# Grove_Base_Shield_for_NodeMCU_v1_0.net
KiCad netlist of a schematic drawn in EAGLE
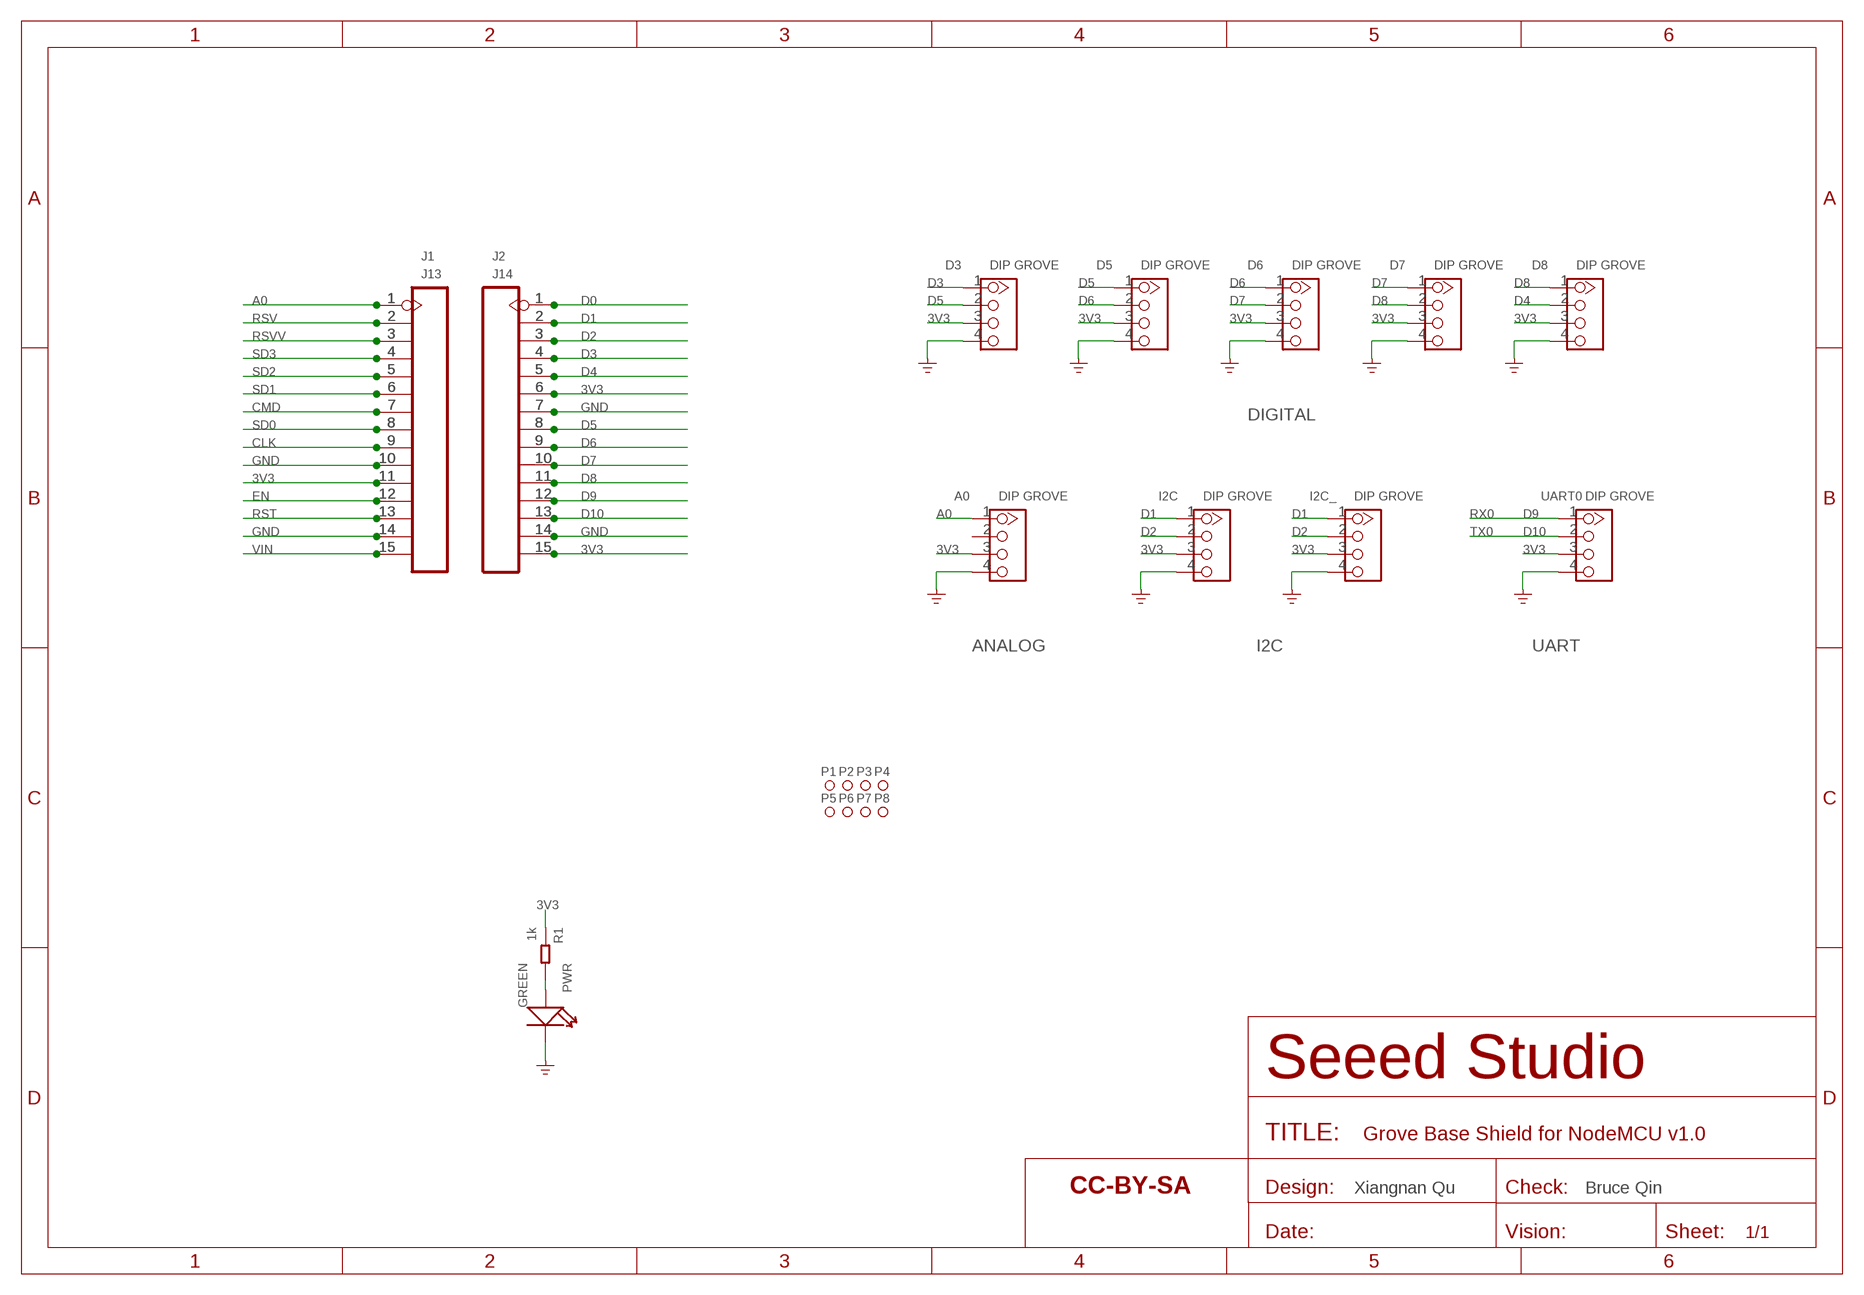
[diagram p0: schematic, sheet 1]

(export (version "E")
  (design (tool "Eeschema 10.0.6"))
  (components
    (comp (ref "A0")
      (value "DIP GROVE")
      (footprint "eagle-import:HW4-2.0")
      (libsource (lib "eagle-import") (part "GROVE-CONNECTOR-DIP-2.0"))
    )
    (comp (ref "D3")
      (value "DIP GROVE")
      (footprint "eagle-import:HW4-2.0")
      (libsource (lib "eagle-import") (part "GROVE-CONNECTOR-DIP-2.0"))
    )
    (comp (ref "D5")
      (value "DIP GROVE")
      (footprint "eagle-import:HW4-2.0")
      (libsource (lib "eagle-import") (part "GROVE-CONNECTOR-DIP-2.0"))
    )
    (comp (ref "D6")
      (value "DIP GROVE")
      (footprint "eagle-import:HW4-2.0")
      (libsource (lib "eagle-import") (part "GROVE-CONNECTOR-DIP-2.0"))
    )
    (comp (ref "D7")
      (value "DIP GROVE")
      (footprint "eagle-import:HW4-2.0")
      (libsource (lib "eagle-import") (part "GROVE-CONNECTOR-DIP-2.0"))
    )
    (comp (ref "D8")
      (value "DIP GROVE")
      (footprint "eagle-import:HW4-2.0")
      (libsource (lib "eagle-import") (part "GROVE-CONNECTOR-DIP-2.0"))
    )
    (comp (ref "I2C")
      (value "DIP GROVE")
      (footprint "eagle-import:HW4-2.0")
      (libsource (lib "eagle-import") (part "GROVE-CONNECTOR-DIP-2.0"))
    )
    (comp (ref "I2C_")
      (value "DIP GROVE")
      (footprint "eagle-import:HW4-2.0")
      (libsource (lib "eagle-import") (part "GROVE-CONNECTOR-DIP-2.0"))
    )
    (comp (ref "J1")
      (value "HEADER-15P'2.54'")
      (footprint "eagle-import:H15-2.54")
      (libsource (lib "eagle-import") (part "HEADER-15P'2.54'"))
    )
    (comp (ref "J2")
      (value "HEADER-15P'2.54'")
      (footprint "eagle-import:H15-2.54")
      (libsource (lib "eagle-import") (part "HEADER-15P'2.54'"))
    )
    (comp (ref "J13")
      (value "HEADER-15P'2.54'")
      (footprint "eagle-import:H15-2.54")
      (libsource (lib "eagle-import") (part "HEADER-15P'2.54'"))
    )
    (comp (ref "J14")
      (value "HEADER-15P'2.54'")
      (footprint "eagle-import:H15-2.54")
      (libsource (lib "eagle-import") (part "HEADER-15P'2.54'"))
    )
    (comp (ref "P1")
      (value "MARK-1.0'ANNULAR'")
      (footprint "eagle-import:ROUND-MARK-1.0")
      (fields (field (name "PARTNO") "DNP"))
      (libsource (lib "eagle-import") (part "MARK-1.0'ANNULAR'"))
    )
    (comp (ref "P2")
      (value "MARK-1.0'ANNULAR'")
      (footprint "eagle-import:ROUND-MARK-1.0")
      (fields (field (name "PARTNO") "DNP"))
      (libsource (lib "eagle-import") (part "MARK-1.0'ANNULAR'"))
    )
    (comp (ref "P3")
      (value "MARK-1.0'ANNULAR'")
      (footprint "eagle-import:ROUND-MARK-1.0")
      (fields (field (name "PARTNO") "DNP"))
      (libsource (lib "eagle-import") (part "MARK-1.0'ANNULAR'"))
    )
    (comp (ref "P4")
      (value "MARK-1.0'ANNULAR'")
      (footprint "eagle-import:ROUND-MARK-1.0")
      (fields (field (name "PARTNO") "DNP"))
      (libsource (lib "eagle-import") (part "MARK-1.0'ANNULAR'"))
    )
    (comp (ref "P5")
      (value "MARK-1.0'ANNULAR'")
      (footprint "eagle-import:ROUND-MARK-1.0")
      (fields (field (name "PARTNO") "DNP"))
      (libsource (lib "eagle-import") (part "MARK-1.0'ANNULAR'"))
    )
    (comp (ref "P6")
      (value "MARK-1.0'ANNULAR'")
      (footprint "eagle-import:ROUND-MARK-1.0")
      (fields (field (name "PARTNO") "DNP"))
      (libsource (lib "eagle-import") (part "MARK-1.0'ANNULAR'"))
    )
    (comp (ref "P7")
      (value "MARK-1.0'ANNULAR'")
      (footprint "eagle-import:ROUND-MARK-1.0")
      (fields (field (name "PARTNO") "DNP"))
      (libsource (lib "eagle-import") (part "MARK-1.0'ANNULAR'"))
    )
    (comp (ref "P8")
      (value "MARK-1.0'ANNULAR'")
      (footprint "eagle-import:ROUND-MARK-1.0")
      (fields (field (name "PARTNO") "DNP"))
      (libsource (lib "eagle-import") (part "MARK-1.0'ANNULAR'"))
    )
    (comp (ref "PWR")
      (value "GREEN")
      (footprint "eagle-import:LED-0603")
      (libsource (lib "eagle-import") (part "LED'0603'"))
    )
    (comp (ref "R1")
      (value "1k")
      (footprint "eagle-import:R0603")
      (libsource (lib "eagle-import") (part "RES-0603"))
    )
    (comp (ref "U$7")
      (value "SEEEDSTUDIO-OPEN-SCH-FRAME")
      (footprint "eagle-import:SEEEDSTUDIO-PCB-FRAME")
      (libsource (lib "eagle-import") (part "SEEEDSTUDIO-OPEN-SCH-FRAME"))
    )
    (comp (ref "UART0")
      (value "DIP GROVE")
      (footprint "eagle-import:HW4-2.0")
      (libsource (lib "eagle-import") (part "GROVE-CONNECTOR-DIP-2.0"))
    )
  )
  (nets
    (net (code "1") (name "/3V3") (class "Default")
      (node (ref "A0") (pin "3") (pinfunction "3_3") (pintype "bidirectional"))
      (node (ref "D3") (pin "3") (pinfunction "3_3") (pintype "bidirectional"))
      (node (ref "D5") (pin "3") (pinfunction "3_3") (pintype "bidirectional"))
      (node (ref "D6") (pin "3") (pinfunction "3_3") (pintype "bidirectional"))
      (node (ref "D7") (pin "3") (pinfunction "3_3") (pintype "bidirectional"))
      (node (ref "D8") (pin "3") (pinfunction "3_3") (pintype "bidirectional"))
      (node (ref "I2C") (pin "3") (pinfunction "3_3") (pintype "bidirectional"))
      (node (ref "I2C_") (pin "3") (pinfunction "3_3") (pintype "bidirectional"))
      (node (ref "J1") (pin "11") (pinfunction "11_11") (pintype "passive"))
      (node (ref "J13") (pin "11") (pinfunction "11_11") (pintype "passive"))
      (node (ref "J14") (pin "15") (pinfunction "15_15") (pintype "passive"))
      (node (ref "J14") (pin "6") (pinfunction "6_6") (pintype "passive"))
      (node (ref "J2") (pin "15") (pinfunction "15_15") (pintype "passive"))
      (node (ref "J2") (pin "6") (pinfunction "6_6") (pintype "passive"))
      (node (ref "R1") (pin "1") (pinfunction "1_1") (pintype "passive"))
      (node (ref "UART0") (pin "3") (pinfunction "3_3") (pintype "bidirectional"))
    )
    (net (code "2") (name "/A0") (class "Default")
      (node (ref "A0") (pin "1") (pinfunction "1_1") (pintype "bidirectional"))
      (node (ref "J1") (pin "1") (pinfunction "1_1") (pintype "passive"))
      (node (ref "J13") (pin "1") (pinfunction "1_1") (pintype "passive"))
    )
    (net (code "3") (name "/CLK") (class "Default")
      (node (ref "J1") (pin "9") (pinfunction "9_9") (pintype "passive"))
      (node (ref "J13") (pin "9") (pinfunction "9_9") (pintype "passive"))
    )
    (net (code "4") (name "/CMD") (class "Default")
      (node (ref "J1") (pin "7") (pinfunction "7_7") (pintype "passive"))
      (node (ref "J13") (pin "7") (pinfunction "7_7") (pintype "passive"))
    )
    (net (code "5") (name "/D0") (class "Default")
      (node (ref "J14") (pin "1") (pinfunction "1_1") (pintype "passive"))
      (node (ref "J2") (pin "1") (pinfunction "1_1") (pintype "passive"))
    )
    (net (code "6") (name "/D1") (class "Default")
      (node (ref "I2C") (pin "1") (pinfunction "1_1") (pintype "bidirectional"))
      (node (ref "I2C_") (pin "1") (pinfunction "1_1") (pintype "bidirectional"))
      (node (ref "J14") (pin "2") (pinfunction "2_2") (pintype "passive"))
      (node (ref "J2") (pin "2") (pinfunction "2_2") (pintype "passive"))
    )
    (net (code "7") (name "/D2") (class "Default")
      (node (ref "I2C") (pin "2") (pinfunction "2_2") (pintype "bidirectional"))
      (node (ref "I2C_") (pin "2") (pinfunction "2_2") (pintype "bidirectional"))
      (node (ref "J14") (pin "3") (pinfunction "3_3") (pintype "passive"))
      (node (ref "J2") (pin "3") (pinfunction "3_3") (pintype "passive"))
    )
    (net (code "8") (name "/D3") (class "Default")
      (node (ref "D3") (pin "1") (pinfunction "1_1") (pintype "bidirectional"))
      (node (ref "J14") (pin "4") (pinfunction "4_4") (pintype "passive"))
      (node (ref "J2") (pin "4") (pinfunction "4_4") (pintype "passive"))
    )
    (net (code "9") (name "/D4") (class "Default")
      (node (ref "D8") (pin "2") (pinfunction "2_2") (pintype "bidirectional"))
      (node (ref "J14") (pin "5") (pinfunction "5_5") (pintype "passive"))
      (node (ref "J2") (pin "5") (pinfunction "5_5") (pintype "passive"))
    )
    (net (code "10") (name "/D5") (class "Default")
      (node (ref "D3") (pin "2") (pinfunction "2_2") (pintype "bidirectional"))
      (node (ref "D5") (pin "1") (pinfunction "1_1") (pintype "bidirectional"))
      (node (ref "J14") (pin "8") (pinfunction "8_8") (pintype "passive"))
      (node (ref "J2") (pin "8") (pinfunction "8_8") (pintype "passive"))
    )
    (net (code "11") (name "/D6") (class "Default")
      (node (ref "D5") (pin "2") (pinfunction "2_2") (pintype "bidirectional"))
      (node (ref "D6") (pin "1") (pinfunction "1_1") (pintype "bidirectional"))
      (node (ref "J14") (pin "9") (pinfunction "9_9") (pintype "passive"))
      (node (ref "J2") (pin "9") (pinfunction "9_9") (pintype "passive"))
    )
    (net (code "12") (name "/D7") (class "Default")
      (node (ref "D6") (pin "2") (pinfunction "2_2") (pintype "bidirectional"))
      (node (ref "D7") (pin "1") (pinfunction "1_1") (pintype "bidirectional"))
      (node (ref "J14") (pin "10") (pinfunction "10_10") (pintype "passive"))
      (node (ref "J2") (pin "10") (pinfunction "10_10") (pintype "passive"))
    )
    (net (code "13") (name "/D8") (class "Default")
      (node (ref "D7") (pin "2") (pinfunction "2_2") (pintype "bidirectional"))
      (node (ref "D8") (pin "1") (pinfunction "1_1") (pintype "bidirectional"))
      (node (ref "J14") (pin "11") (pinfunction "11_11") (pintype "passive"))
      (node (ref "J2") (pin "11") (pinfunction "11_11") (pintype "passive"))
    )
    (net (code "14") (name "/D9") (class "Default")
      (node (ref "J14") (pin "12") (pinfunction "12_12") (pintype "passive"))
      (node (ref "J2") (pin "12") (pinfunction "12_12") (pintype "passive"))
      (node (ref "UART0") (pin "1") (pinfunction "1_1") (pintype "bidirectional"))
    )
    (net (code "15") (name "/D10") (class "Default")
      (node (ref "J14") (pin "13") (pinfunction "13_13") (pintype "passive"))
      (node (ref "J2") (pin "13") (pinfunction "13_13") (pintype "passive"))
      (node (ref "UART0") (pin "2") (pinfunction "2_2") (pintype "bidirectional"))
    )
    (net (code "16") (name "/EN") (class "Default")
      (node (ref "J1") (pin "12") (pinfunction "12_12") (pintype "passive"))
      (node (ref "J13") (pin "12") (pinfunction "12_12") (pintype "passive"))
    )
    (net (code "17") (name "/RST") (class "Default")
      (node (ref "J1") (pin "13") (pinfunction "13_13") (pintype "passive"))
      (node (ref "J13") (pin "13") (pinfunction "13_13") (pintype "passive"))
    )
    (net (code "18") (name "/RSV") (class "Default")
      (node (ref "J1") (pin "2") (pinfunction "2_2") (pintype "passive"))
      (node (ref "J13") (pin "2") (pinfunction "2_2") (pintype "passive"))
    )
    (net (code "19") (name "/RSVV") (class "Default")
      (node (ref "J1") (pin "3") (pinfunction "3_3") (pintype "passive"))
      (node (ref "J13") (pin "3") (pinfunction "3_3") (pintype "passive"))
    )
    (net (code "20") (name "/SD0") (class "Default")
      (node (ref "J1") (pin "8") (pinfunction "8_8") (pintype "passive"))
      (node (ref "J13") (pin "8") (pinfunction "8_8") (pintype "passive"))
    )
    (net (code "21") (name "/SD1") (class "Default")
      (node (ref "J1") (pin "6") (pinfunction "6_6") (pintype "passive"))
      (node (ref "J13") (pin "6") (pinfunction "6_6") (pintype "passive"))
    )
    (net (code "22") (name "/SD2") (class "Default")
      (node (ref "J1") (pin "5") (pinfunction "5_5") (pintype "passive"))
      (node (ref "J13") (pin "5") (pinfunction "5_5") (pintype "passive"))
    )
    (net (code "23") (name "/SD3") (class "Default")
      (node (ref "J1") (pin "4") (pinfunction "4_4") (pintype "passive"))
      (node (ref "J13") (pin "4") (pinfunction "4_4") (pintype "passive"))
    )
    (net (code "24") (name "/VIN") (class "Default")
      (node (ref "J1") (pin "15") (pinfunction "15_15") (pintype "passive"))
      (node (ref "J13") (pin "15") (pinfunction "15_15") (pintype "passive"))
    )
    (net (code "25") (name "GND_POWER") (class "Default")
      (node (ref "A0") (pin "4") (pinfunction "4_4") (pintype "bidirectional"))
      (node (ref "D3") (pin "4") (pinfunction "4_4") (pintype "bidirectional"))
      (node (ref "D5") (pin "4") (pinfunction "4_4") (pintype "bidirectional"))
      (node (ref "D6") (pin "4") (pinfunction "4_4") (pintype "bidirectional"))
      (node (ref "D7") (pin "4") (pinfunction "4_4") (pintype "bidirectional"))
      (node (ref "D8") (pin "4") (pinfunction "4_4") (pintype "bidirectional"))
      (node (ref "I2C") (pin "4") (pinfunction "4_4") (pintype "bidirectional"))
      (node (ref "I2C_") (pin "4") (pinfunction "4_4") (pintype "bidirectional"))
      (node (ref "J1") (pin "10") (pinfunction "10_10") (pintype "passive"))
      (node (ref "J1") (pin "14") (pinfunction "14_14") (pintype "passive"))
      (node (ref "J13") (pin "10") (pinfunction "10_10") (pintype "passive"))
      (node (ref "J13") (pin "14") (pinfunction "14_14") (pintype "passive"))
      (node (ref "J14") (pin "14") (pinfunction "14_14") (pintype "passive"))
      (node (ref "J14") (pin "7") (pinfunction "7_7") (pintype "passive"))
      (node (ref "J2") (pin "14") (pinfunction "14_14") (pintype "passive"))
      (node (ref "J2") (pin "7") (pinfunction "7_7") (pintype "passive"))
      (node (ref "PWR") (pin "-") (pinfunction "-_-") (pintype "passive"))
      (node (ref "UART0") (pin "4") (pinfunction "4_4") (pintype "bidirectional"))
    )
    (net (code "26") (name "Net-(PWR-Pad+)") (class "Default")
      (node (ref "PWR") (pin "+") (pinfunction "+_+") (pintype "passive"))
      (node (ref "R1") (pin "2") (pinfunction "2_2") (pintype "passive"))
    )
    (net (code "27") (name "unconnected-(A0-Pad2)") (class "Default")
      (node (ref "A0") (pin "2") (pinfunction "2_2") (pintype "bidirectional"))
    )
  )
)
